# snc98_Display_15x7-Seg_1-digit_SC52.net
KiCad netlist of a schematic drawn in EAGLE
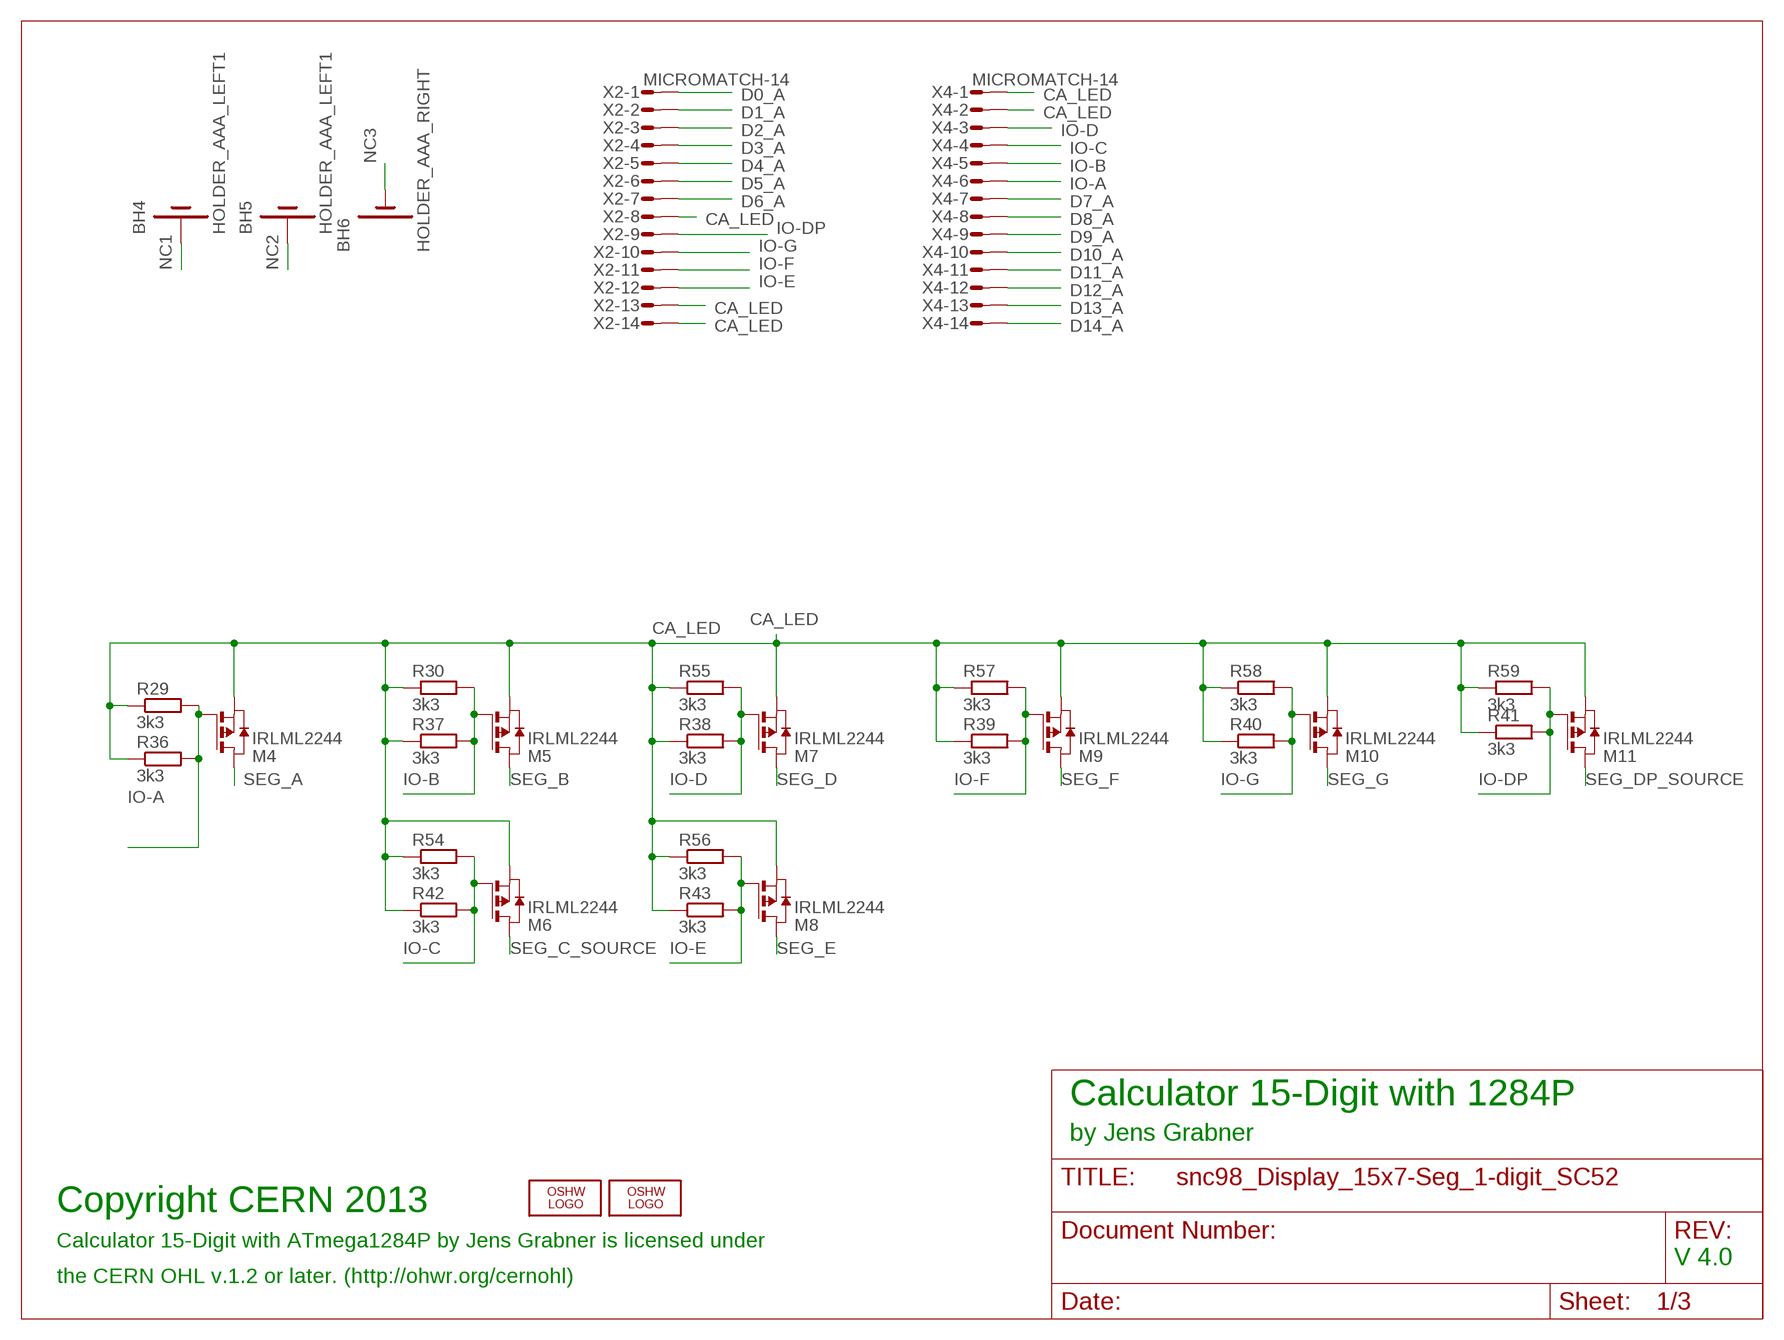
[diagram p0: schematic, sheet 1]
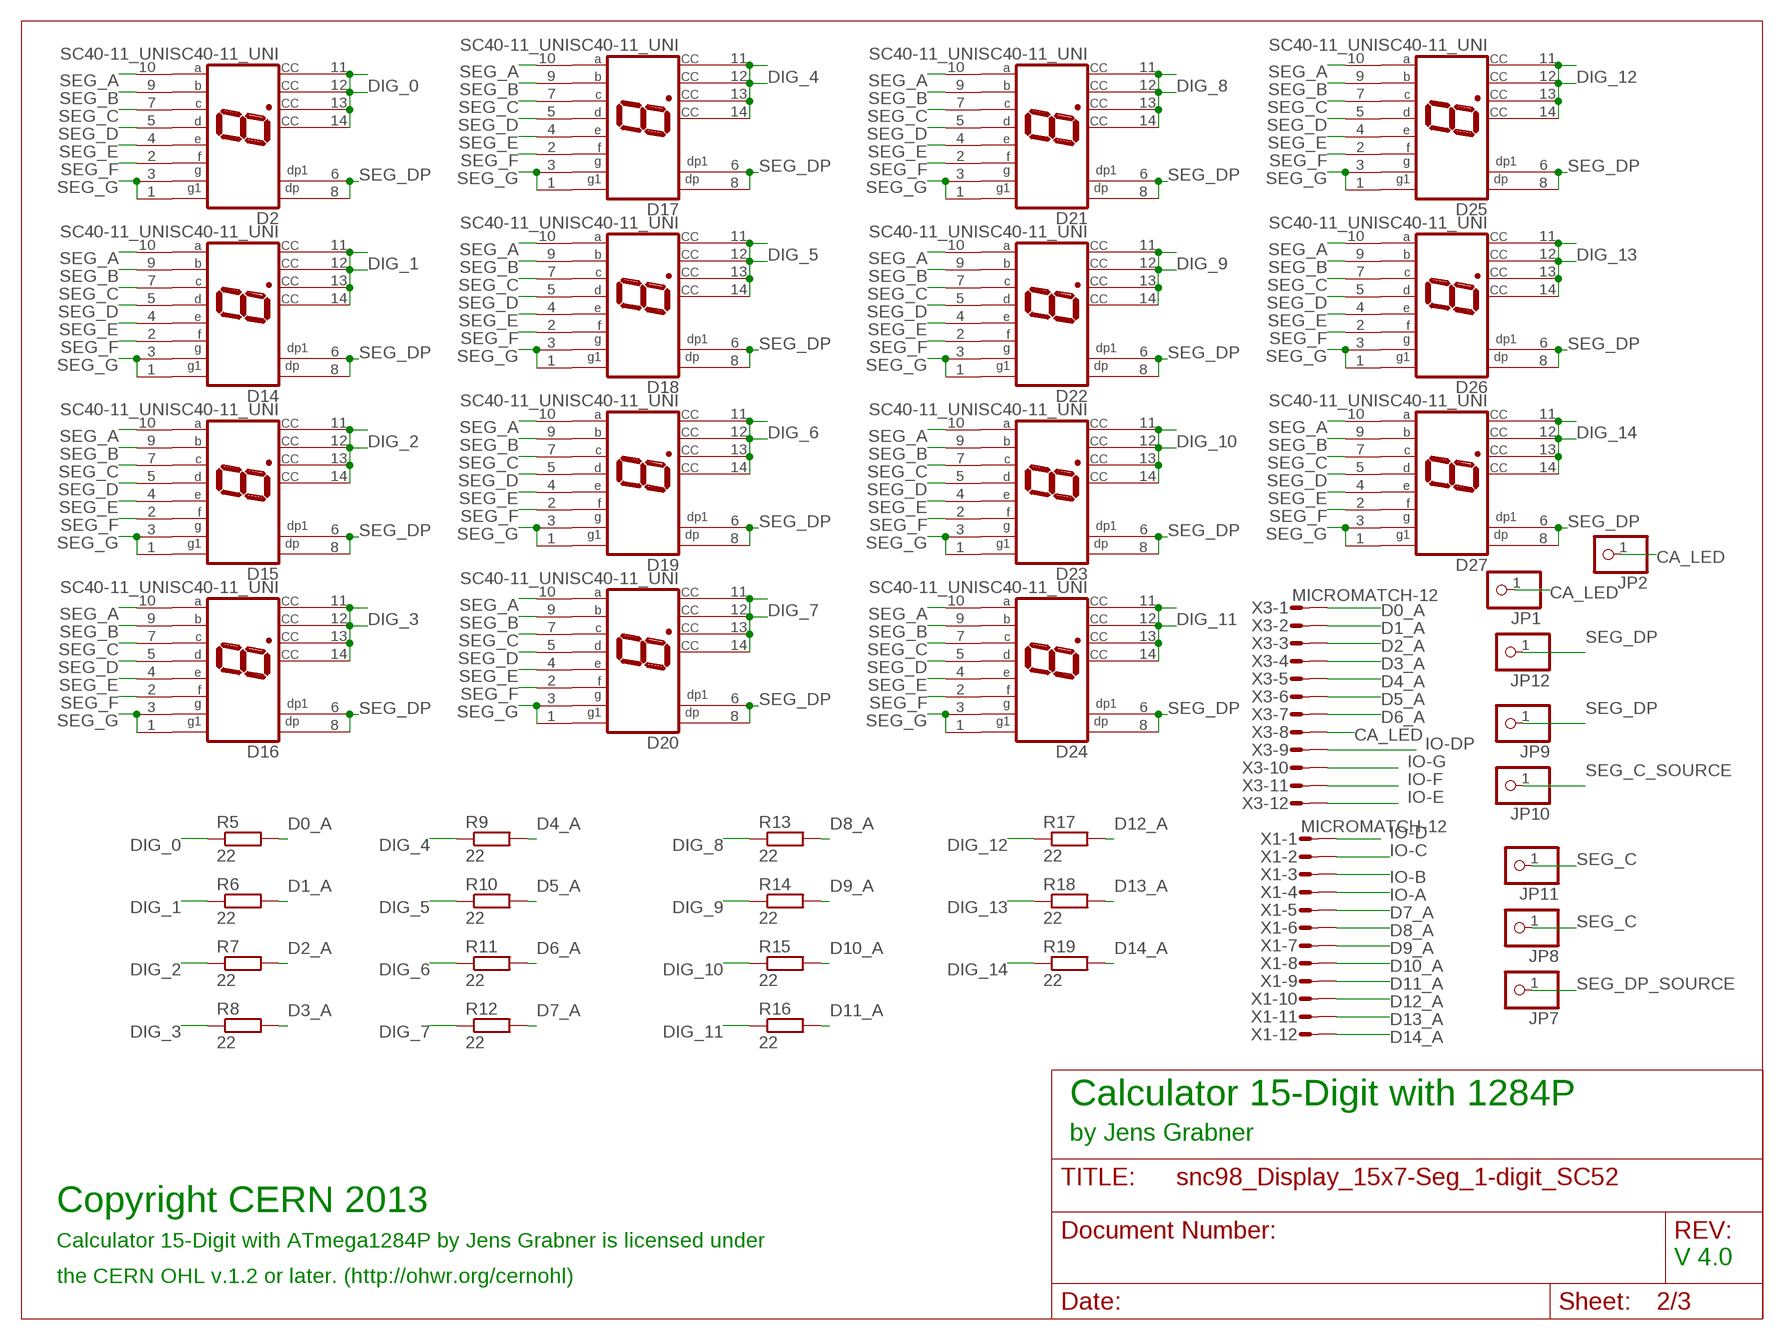
[diagram p1: schematic, sheet 2]
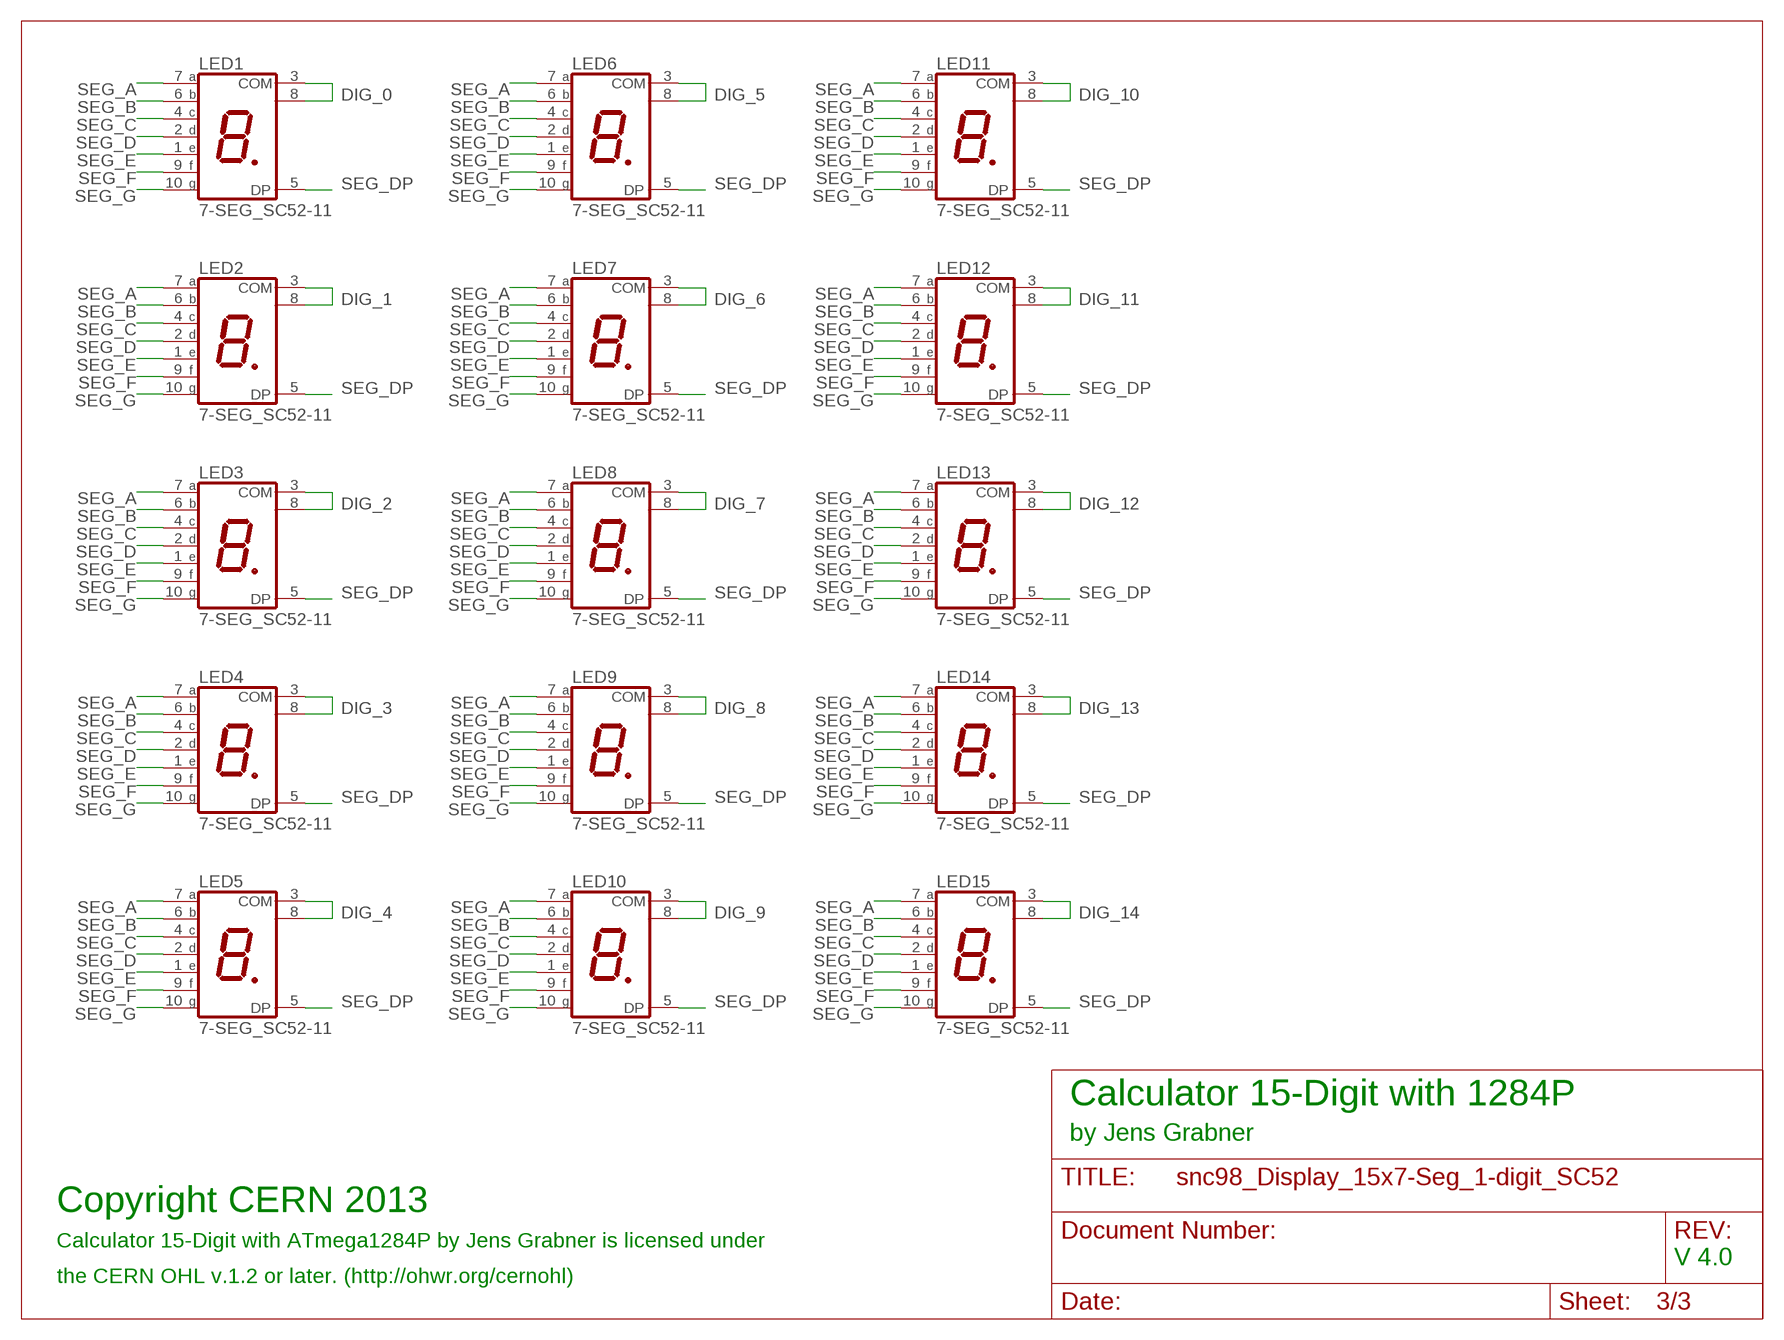
[diagram p2: schematic, sheet 3]

(export (version "E")
  (design (tool "Eeschema 10.0.6"))
  (components
    (comp (ref "LED1")
      (value "7-SEG_SC52-11")
      (footprint "eagle-import:SA52-11")
      (libsource (lib "eagle-import") (part "7-SEG_SA52-11"))
    )
    (comp (ref "LED2")
      (value "7-SEG_SC52-11")
      (footprint "eagle-import:SA52-11")
      (libsource (lib "eagle-import") (part "7-SEG_SA52-11"))
    )
    (comp (ref "LED3")
      (value "7-SEG_SC52-11")
      (footprint "eagle-import:SA52-11")
      (libsource (lib "eagle-import") (part "7-SEG_SA52-11"))
    )
    (comp (ref "LED4")
      (value "7-SEG_SC52-11")
      (footprint "eagle-import:SA52-11")
      (libsource (lib "eagle-import") (part "7-SEG_SA52-11"))
    )
    (comp (ref "LED5")
      (value "7-SEG_SC52-11")
      (footprint "eagle-import:SA52-11")
      (libsource (lib "eagle-import") (part "7-SEG_SA52-11"))
    )
    (comp (ref "LED6")
      (value "7-SEG_SC52-11")
      (footprint "eagle-import:SA52-11")
      (libsource (lib "eagle-import") (part "7-SEG_SA52-11"))
    )
    (comp (ref "LED7")
      (value "7-SEG_SC52-11")
      (footprint "eagle-import:SA52-11")
      (libsource (lib "eagle-import") (part "7-SEG_SA52-11"))
    )
    (comp (ref "LED8")
      (value "7-SEG_SC52-11")
      (footprint "eagle-import:SA52-11")
      (libsource (lib "eagle-import") (part "7-SEG_SA52-11"))
    )
    (comp (ref "LED9")
      (value "7-SEG_SC52-11")
      (footprint "eagle-import:SA52-11")
      (libsource (lib "eagle-import") (part "7-SEG_SA52-11"))
    )
    (comp (ref "LED10")
      (value "7-SEG_SC52-11")
      (footprint "eagle-import:SA52-11")
      (libsource (lib "eagle-import") (part "7-SEG_SA52-11"))
    )
    (comp (ref "LED11")
      (value "7-SEG_SC52-11")
      (footprint "eagle-import:SA52-11")
      (libsource (lib "eagle-import") (part "7-SEG_SA52-11"))
    )
    (comp (ref "LED12")
      (value "7-SEG_SC52-11")
      (footprint "eagle-import:SA52-11")
      (libsource (lib "eagle-import") (part "7-SEG_SA52-11"))
    )
    (comp (ref "LED13")
      (value "7-SEG_SC52-11")
      (footprint "eagle-import:SA52-11")
      (libsource (lib "eagle-import") (part "7-SEG_SA52-11"))
    )
    (comp (ref "LED14")
      (value "7-SEG_SC52-11")
      (footprint "eagle-import:SA52-11")
      (libsource (lib "eagle-import") (part "7-SEG_SA52-11"))
    )
    (comp (ref "LED15")
      (value "7-SEG_SC52-11")
      (footprint "eagle-import:SA52-11")
      (libsource (lib "eagle-import") (part "7-SEG_SA52-11"))
    )
    (comp (ref "D2")
      (value "SC40-11_UNISC40-11_UNI")
      (footprint "eagle-import:10MM_UNI")
      (libsource (lib "eagle-import") (part "SC40-11_UNISC40-11_UNI"))
    )
    (comp (ref "D14")
      (value "SC40-11_UNISC40-11_UNI")
      (footprint "eagle-import:10MM_UNI")
      (libsource (lib "eagle-import") (part "SC40-11_UNISC40-11_UNI"))
    )
    (comp (ref "D15")
      (value "SC40-11_UNISC40-11_UNI")
      (footprint "eagle-import:10MM_UNI")
      (libsource (lib "eagle-import") (part "SC40-11_UNISC40-11_UNI"))
    )
    (comp (ref "D16")
      (value "SC40-11_UNISC40-11_UNI")
      (footprint "eagle-import:10MM_UNI")
      (libsource (lib "eagle-import") (part "SC40-11_UNISC40-11_UNI"))
    )
    (comp (ref "D17")
      (value "SC40-11_UNISC40-11_UNI")
      (footprint "eagle-import:10MM_UNI")
      (libsource (lib "eagle-import") (part "SC40-11_UNISC40-11_UNI"))
    )
    (comp (ref "D18")
      (value "SC40-11_UNISC40-11_UNI")
      (footprint "eagle-import:10MM_UNI")
      (libsource (lib "eagle-import") (part "SC40-11_UNISC40-11_UNI"))
    )
    (comp (ref "D19")
      (value "SC40-11_UNISC40-11_UNI")
      (footprint "eagle-import:10MM_UNI")
      (libsource (lib "eagle-import") (part "SC40-11_UNISC40-11_UNI"))
    )
    (comp (ref "D20")
      (value "SC40-11_UNISC40-11_UNI")
      (footprint "eagle-import:10MM_UNI")
      (libsource (lib "eagle-import") (part "SC40-11_UNISC40-11_UNI"))
    )
    (comp (ref "D21")
      (value "SC40-11_UNISC40-11_UNI")
      (footprint "eagle-import:10MM_UNI")
      (libsource (lib "eagle-import") (part "SC40-11_UNISC40-11_UNI"))
    )
    (comp (ref "D22")
      (value "SC40-11_UNISC40-11_UNI")
      (footprint "eagle-import:10MM_UNI")
      (libsource (lib "eagle-import") (part "SC40-11_UNISC40-11_UNI"))
    )
    (comp (ref "D23")
      (value "SC40-11_UNISC40-11_UNI")
      (footprint "eagle-import:10MM_UNI")
      (libsource (lib "eagle-import") (part "SC40-11_UNISC40-11_UNI"))
    )
    (comp (ref "D24")
      (value "SC40-11_UNISC40-11_UNI")
      (footprint "eagle-import:10MM_UNI")
      (libsource (lib "eagle-import") (part "SC40-11_UNISC40-11_UNI"))
    )
    (comp (ref "D25")
      (value "SC40-11_UNISC40-11_UNI")
      (footprint "eagle-import:10MM_UNI")
      (libsource (lib "eagle-import") (part "SC40-11_UNISC40-11_UNI"))
    )
    (comp (ref "D26")
      (value "SC40-11_UNISC40-11_UNI")
      (footprint "eagle-import:10MM_UNI")
      (libsource (lib "eagle-import") (part "SC40-11_UNISC40-11_UNI"))
    )
    (comp (ref "D27")
      (value "SC40-11_UNISC40-11_UNI")
      (footprint "eagle-import:10MM_UNI")
      (libsource (lib "eagle-import") (part "SC40-11_UNISC40-11_UNI"))
    )
    (comp (ref "JP1")
      (value "PINHD-1X1")
      (footprint "eagle-import:1X01")
      (libsource (lib "eagle-import") (part "PINHD-1X1"))
    )
    (comp (ref "JP2")
      (value "PINHD-1X1")
      (footprint "eagle-import:1X01")
      (libsource (lib "eagle-import") (part "PINHD-1X1"))
    )
    (comp (ref "JP7")
      (value "PINHD-1X1")
      (footprint "eagle-import:1X01")
      (libsource (lib "eagle-import") (part "PINHD-1X1"))
    )
    (comp (ref "JP8")
      (value "PINHD-1X1")
      (footprint "eagle-import:1X01")
      (libsource (lib "eagle-import") (part "PINHD-1X1"))
    )
    (comp (ref "JP9")
      (value "PINHD-1X1")
      (footprint "eagle-import:1X01")
      (libsource (lib "eagle-import") (part "PINHD-1X1"))
    )
    (comp (ref "JP10")
      (value "PINHD-1X1")
      (footprint "eagle-import:1X01")
      (libsource (lib "eagle-import") (part "PINHD-1X1"))
    )
    (comp (ref "JP11")
      (value "PINHD-1X1")
      (footprint "eagle-import:1X01")
      (libsource (lib "eagle-import") (part "PINHD-1X1"))
    )
    (comp (ref "JP12")
      (value "PINHD-1X1")
      (footprint "eagle-import:1X01")
      (libsource (lib "eagle-import") (part "PINHD-1X1"))
    )
    (comp (ref "R5")
      (value "22")
      (footprint "eagle-import:R1210")
      (libsource (lib "eagle-import") (part "R-EU_R1210"))
    )
    (comp (ref "R6")
      (value "22")
      (footprint "eagle-import:R1210")
      (libsource (lib "eagle-import") (part "R-EU_R1210"))
    )
    (comp (ref "R7")
      (value "22")
      (footprint "eagle-import:R1210")
      (libsource (lib "eagle-import") (part "R-EU_R1210"))
    )
    (comp (ref "R8")
      (value "22")
      (footprint "eagle-import:R1210")
      (libsource (lib "eagle-import") (part "R-EU_R1210"))
    )
    (comp (ref "R9")
      (value "22")
      (footprint "eagle-import:R1210")
      (libsource (lib "eagle-import") (part "R-EU_R1210"))
    )
    (comp (ref "R10")
      (value "22")
      (footprint "eagle-import:R1210")
      (libsource (lib "eagle-import") (part "R-EU_R1210"))
    )
    (comp (ref "R11")
      (value "22")
      (footprint "eagle-import:R1210")
      (libsource (lib "eagle-import") (part "R-EU_R1210"))
    )
    (comp (ref "R12")
      (value "22")
      (footprint "eagle-import:R1210")
      (libsource (lib "eagle-import") (part "R-EU_R1210"))
    )
    (comp (ref "R13")
      (value "22")
      (footprint "eagle-import:R1210")
      (libsource (lib "eagle-import") (part "R-EU_R1210"))
    )
    (comp (ref "R14")
      (value "22")
      (footprint "eagle-import:R1210")
      (libsource (lib "eagle-import") (part "R-EU_R1210"))
    )
    (comp (ref "R15")
      (value "22")
      (footprint "eagle-import:R1210")
      (libsource (lib "eagle-import") (part "R-EU_R1210"))
    )
    (comp (ref "R16")
      (value "22")
      (footprint "eagle-import:R1210")
      (libsource (lib "eagle-import") (part "R-EU_R1210"))
    )
    (comp (ref "R17")
      (value "22")
      (footprint "eagle-import:R1210")
      (libsource (lib "eagle-import") (part "R-EU_R1210"))
    )
    (comp (ref "R18")
      (value "22")
      (footprint "eagle-import:R1210")
      (libsource (lib "eagle-import") (part "R-EU_R1210"))
    )
    (comp (ref "R19")
      (value "22")
      (footprint "eagle-import:R1210")
      (libsource (lib "eagle-import") (part "R-EU_R1210"))
    )
    (comp (ref "X1")
      (value "MICROMATCH-12")
      (footprint "eagle-import:MICROMATCH-12")
      (fields (field (name "MF") "FARNELL") (field (name "MPN") "8-215464-2"))
      (libsource (lib "eagle-import") (part "MICROMATCH-12"))
    )
    (comp (ref "X3")
      (value "MICROMATCH-12")
      (footprint "eagle-import:MICROMATCH-12")
      (fields (field (name "MF") "FARNELL") (field (name "MPN") "8-215464-2"))
      (libsource (lib "eagle-import") (part "MICROMATCH-12"))
    )
    (comp (ref "BH4")
      (value "HOLDER_AAA_LEFT1")
      (footprint "eagle-import:BATTERY-AAA-LEFT")
      (libsource (lib "eagle-import") (part "HOLDER_AAA_LEFT1"))
    )
    (comp (ref "BH5")
      (value "HOLDER_AAA_LEFT1")
      (footprint "eagle-import:BATTERY-AAA-LEFT")
      (libsource (lib "eagle-import") (part "HOLDER_AAA_LEFT1"))
    )
    (comp (ref "BH6")
      (value "HOLDER_AAA_RIGHT")
      (footprint "eagle-import:BATTERY-AAA-RIGHT")
      (libsource (lib "eagle-import") (part "HOLDER_AAA_RIGHT"))
    )
    (comp (ref "LOGO1")
      (value "OSHW_LOGO_8MILX0150-NT")
      (footprint "eagle-import:OSHW_8X150_NOTEXT")
      (libsource (lib "eagle-import") (part "OSHW_LOGO_8MILX0150-NT"))
    )
    (comp (ref "LOGO3")
      (value "OSHW_LOGO_6MILX0100-NT")
      (footprint "eagle-import:OSHW_6X100_NOTEXT")
      (libsource (lib "eagle-import") (part "OSHW_LOGO_6MILX0100-NT"))
    )
    (comp (ref "M4")
      (value "IRLML2244")
      (footprint "eagle-import:SOT-23")
      (libsource (lib "eagle-import") (part "IRLML6402"))
    )
    (comp (ref "M5")
      (value "IRLML2244")
      (footprint "eagle-import:SOT-23")
      (libsource (lib "eagle-import") (part "IRLML6402"))
    )
    (comp (ref "M6")
      (value "IRLML2244")
      (footprint "eagle-import:SOT-23")
      (libsource (lib "eagle-import") (part "IRLML6402"))
    )
    (comp (ref "M7")
      (value "IRLML2244")
      (footprint "eagle-import:SOT-23")
      (libsource (lib "eagle-import") (part "IRLML6402"))
    )
    (comp (ref "M8")
      (value "IRLML2244")
      (footprint "eagle-import:SOT-23")
      (libsource (lib "eagle-import") (part "IRLML6402"))
    )
    (comp (ref "M9")
      (value "IRLML2244")
      (footprint "eagle-import:SOT-23")
      (libsource (lib "eagle-import") (part "IRLML6402"))
    )
    (comp (ref "M10")
      (value "IRLML2244")
      (footprint "eagle-import:SOT-23")
      (libsource (lib "eagle-import") (part "IRLML6402"))
    )
    (comp (ref "M11")
      (value "IRLML2244")
      (footprint "eagle-import:SOT-23")
      (libsource (lib "eagle-import") (part "IRLML6402"))
    )
    (comp (ref "R29")
      (value "3k3")
      (footprint "eagle-import:0204_5")
      (libsource (lib "eagle-import") (part "R-EU_0204/5"))
    )
    (comp (ref "R30")
      (value "3k3")
      (footprint "eagle-import:0204_5")
      (libsource (lib "eagle-import") (part "R-EU_0204/5"))
    )
    (comp (ref "R36")
      (value "3k3")
      (footprint "eagle-import:R1206")
      (libsource (lib "eagle-import") (part "R-EU_R1206"))
    )
    (comp (ref "R37")
      (value "3k3")
      (footprint "eagle-import:R1206")
      (libsource (lib "eagle-import") (part "R-EU_R1206"))
    )
    (comp (ref "R38")
      (value "3k3")
      (footprint "eagle-import:R1206")
      (libsource (lib "eagle-import") (part "R-EU_R1206"))
    )
    (comp (ref "R39")
      (value "3k3")
      (footprint "eagle-import:R1206")
      (libsource (lib "eagle-import") (part "R-EU_R1206"))
    )
    (comp (ref "R40")
      (value "3k3")
      (footprint "eagle-import:R1206")
      (libsource (lib "eagle-import") (part "R-EU_R1206"))
    )
    (comp (ref "R41")
      (value "3k3")
      (footprint "eagle-import:R1206")
      (libsource (lib "eagle-import") (part "R-EU_R1206"))
    )
    (comp (ref "R42")
      (value "3k3")
      (footprint "eagle-import:R1206")
      (libsource (lib "eagle-import") (part "R-EU_R1206"))
    )
    (comp (ref "R43")
      (value "3k3")
      (footprint "eagle-import:R1206")
      (libsource (lib "eagle-import") (part "R-EU_R1206"))
    )
    (comp (ref "R54")
      (value "3k3")
      (footprint "eagle-import:0204_5")
      (libsource (lib "eagle-import") (part "R-EU_0204/5"))
    )
    (comp (ref "R55")
      (value "3k3")
      (footprint "eagle-import:0204_5")
      (libsource (lib "eagle-import") (part "R-EU_0204/5"))
    )
    (comp (ref "R56")
      (value "3k3")
      (footprint "eagle-import:0204_5")
      (libsource (lib "eagle-import") (part "R-EU_0204/5"))
    )
    (comp (ref "R57")
      (value "3k3")
      (footprint "eagle-import:0204_5")
      (libsource (lib "eagle-import") (part "R-EU_0204/5"))
    )
    (comp (ref "R58")
      (value "3k3")
      (footprint "eagle-import:0204_5")
      (libsource (lib "eagle-import") (part "R-EU_0204/5"))
    )
    (comp (ref "R59")
      (value "3k3")
      (footprint "eagle-import:0204_5")
      (libsource (lib "eagle-import") (part "R-EU_0204/5"))
    )
    (comp (ref "X2")
      (value "MICROMATCH-14")
      (footprint "eagle-import:MICROMATCH-14")
      (fields (field (name "MF") "FARNELL") (field (name "MPN") "8-215464-4"))
      (libsource (lib "eagle-import") (part "MICROMATCH-14"))
    )
    (comp (ref "X4")
      (value "MICROMATCH-14")
      (footprint "eagle-import:MICROMATCH-14")
      (fields (field (name "MF") "FARNELL") (field (name "MPN") "8-215464-4"))
      (libsource (lib "eagle-import") (part "MICROMATCH-14"))
    )
  )
  (nets
    (net (code "1") (name "CA_LED") (class "Default")
      (node (ref "JP1") (pin "1") (pinfunction "1_1") (pintype "passive"))
      (node (ref "JP2") (pin "1") (pinfunction "1_1") (pintype "passive"))
      (node (ref "M10") (pin "2") (pinfunction "S_2") (pintype "passive"))
      (node (ref "M11") (pin "2") (pinfunction "S_2") (pintype "passive"))
      (node (ref "M4") (pin "2") (pinfunction "S_2") (pintype "passive"))
      (node (ref "M5") (pin "2") (pinfunction "S_2") (pintype "passive"))
      (node (ref "M6") (pin "2") (pinfunction "S_2") (pintype "passive"))
      (node (ref "M7") (pin "2") (pinfunction "S_2") (pintype "passive"))
      (node (ref "M8") (pin "2") (pinfunction "S_2") (pintype "passive"))
      (node (ref "M9") (pin "2") (pinfunction "S_2") (pintype "passive"))
      (node (ref "R29") (pin "1") (pinfunction "1_1") (pintype "passive"))
      (node (ref "R30") (pin "1") (pinfunction "1_1") (pintype "passive"))
      (node (ref "R36") (pin "1") (pinfunction "1_1") (pintype "passive"))
      (node (ref "R37") (pin "1") (pinfunction "1_1") (pintype "passive"))
      (node (ref "R38") (pin "1") (pinfunction "1_1") (pintype "passive"))
      (node (ref "R39") (pin "1") (pinfunction "1_1") (pintype "passive"))
      (node (ref "R40") (pin "1") (pinfunction "1_1") (pintype "passive"))
      (node (ref "R41") (pin "1") (pinfunction "1_1") (pintype "passive"))
      (node (ref "R42") (pin "1") (pinfunction "1_1") (pintype "passive"))
      (node (ref "R43") (pin "1") (pinfunction "1_1") (pintype "passive"))
      (node (ref "R54") (pin "1") (pinfunction "1_1") (pintype "passive"))
      (node (ref "R55") (pin "1") (pinfunction "1_1") (pintype "passive"))
      (node (ref "R56") (pin "1") (pinfunction "1_1") (pintype "passive"))
      (node (ref "R57") (pin "1") (pinfunction "1_1") (pintype "passive"))
      (node (ref "R58") (pin "1") (pinfunction "1_1") (pintype "passive"))
      (node (ref "R59") (pin "1") (pinfunction "1_1") (pintype "passive"))
      (node (ref "X2") (pin "13") (pinfunction "S_13") (pintype "passive"))
      (node (ref "X2") (pin "14") (pinfunction "S_14") (pintype "passive"))
      (node (ref "X2") (pin "8") (pinfunction "S_8") (pintype "passive"))
      (node (ref "X3") (pin "8") (pinfunction "S_8") (pintype "passive"))
      (node (ref "X4") (pin "1") (pinfunction "S_1") (pintype "passive"))
      (node (ref "X4") (pin "2") (pinfunction "S_2") (pintype "passive"))
    )
    (net (code "2") (name "D0_A") (class "Default")
      (node (ref "R5") (pin "2") (pinfunction "2_2") (pintype "passive"))
      (node (ref "X2") (pin "1") (pinfunction "S_1") (pintype "passive"))
      (node (ref "X3") (pin "1") (pinfunction "S_1") (pintype "passive"))
    )
    (net (code "3") (name "D1_A") (class "Default")
      (node (ref "R6") (pin "2") (pinfunction "2_2") (pintype "passive"))
      (node (ref "X2") (pin "2") (pinfunction "S_2") (pintype "passive"))
      (node (ref "X3") (pin "2") (pinfunction "S_2") (pintype "passive"))
    )
    (net (code "4") (name "D2_A") (class "Default")
      (node (ref "R7") (pin "2") (pinfunction "2_2") (pintype "passive"))
      (node (ref "X2") (pin "3") (pinfunction "S_3") (pintype "passive"))
      (node (ref "X3") (pin "3") (pinfunction "S_3") (pintype "passive"))
    )
    (net (code "5") (name "D3_A") (class "Default")
      (node (ref "R8") (pin "2") (pinfunction "2_2") (pintype "passive"))
      (node (ref "X2") (pin "4") (pinfunction "S_4") (pintype "passive"))
      (node (ref "X3") (pin "4") (pinfunction "S_4") (pintype "passive"))
    )
    (net (code "6") (name "D4_A") (class "Default")
      (node (ref "R9") (pin "2") (pinfunction "2_2") (pintype "passive"))
      (node (ref "X2") (pin "5") (pinfunction "S_5") (pintype "passive"))
      (node (ref "X3") (pin "5") (pinfunction "S_5") (pintype "passive"))
    )
    (net (code "7") (name "D5_A") (class "Default")
      (node (ref "R10") (pin "2") (pinfunction "2_2") (pintype "passive"))
      (node (ref "X2") (pin "6") (pinfunction "S_6") (pintype "passive"))
      (node (ref "X3") (pin "6") (pinfunction "S_6") (pintype "passive"))
    )
    (net (code "8") (name "D6_A") (class "Default")
      (node (ref "R11") (pin "2") (pinfunction "2_2") (pintype "passive"))
      (node (ref "X2") (pin "7") (pinfunction "S_7") (pintype "passive"))
      (node (ref "X3") (pin "7") (pinfunction "S_7") (pintype "passive"))
    )
    (net (code "9") (name "D7_A") (class "Default")
      (node (ref "R12") (pin "2") (pinfunction "2_2") (pintype "passive"))
      (node (ref "X1") (pin "5") (pinfunction "S_5") (pintype "passive"))
      (node (ref "X4") (pin "7") (pinfunction "S_7") (pintype "passive"))
    )
    (net (code "10") (name "D8_A") (class "Default")
      (node (ref "R13") (pin "2") (pinfunction "2_2") (pintype "passive"))
      (node (ref "X1") (pin "6") (pinfunction "S_6") (pintype "passive"))
      (node (ref "X4") (pin "8") (pinfunction "S_8") (pintype "passive"))
    )
    (net (code "11") (name "D9_A") (class "Default")
      (node (ref "R14") (pin "2") (pinfunction "2_2") (pintype "passive"))
      (node (ref "X1") (pin "7") (pinfunction "S_7") (pintype "passive"))
      (node (ref "X4") (pin "9") (pinfunction "S_9") (pintype "passive"))
    )
    (net (code "12") (name "D10_A") (class "Default")
      (node (ref "R15") (pin "2") (pinfunction "2_2") (pintype "passive"))
      (node (ref "X1") (pin "8") (pinfunction "S_8") (pintype "passive"))
      (node (ref "X4") (pin "10") (pinfunction "S_10") (pintype "passive"))
    )
    (net (code "13") (name "D11_A") (class "Default")
      (node (ref "R16") (pin "2") (pinfunction "2_2") (pintype "passive"))
      (node (ref "X1") (pin "9") (pinfunction "S_9") (pintype "passive"))
      (node (ref "X4") (pin "11") (pinfunction "S_11") (pintype "passive"))
    )
    (net (code "14") (name "D12_A") (class "Default")
      (node (ref "R17") (pin "2") (pinfunction "2_2") (pintype "passive"))
      (node (ref "X1") (pin "10") (pinfunction "S_10") (pintype "passive"))
      (node (ref "X4") (pin "12") (pinfunction "S_12") (pintype "passive"))
    )
    (net (code "15") (name "D13_A") (class "Default")
      (node (ref "R18") (pin "2") (pinfunction "2_2") (pintype "passive"))
      (node (ref "X1") (pin "11") (pinfunction "S_11") (pintype "passive"))
      (node (ref "X4") (pin "13") (pinfunction "S_13") (pintype "passive"))
    )
    (net (code "16") (name "D14_A") (class "Default")
      (node (ref "R19") (pin "2") (pinfunction "2_2") (pintype "passive"))
      (node (ref "X1") (pin "12") (pinfunction "S_12") (pintype "passive"))
      (node (ref "X4") (pin "14") (pinfunction "S_14") (pintype "passive"))
    )
    (net (code "17") (name "DIG_0") (class "Default")
      (node (ref "D2") (pin "11") (pinfunction "CC1_11") (pintype "passive"))
      (node (ref "D2") (pin "12") (pinfunction "CC2_12") (pintype "passive"))
      (node (ref "D2") (pin "13") (pinfunction "CC3_13") (pintype "passive"))
      (node (ref "D2") (pin "14") (pinfunction "CC4_14") (pintype "passive"))
      (node (ref "LED1") (pin "3") (pinfunction "COM_3") (pintype "passive"))
      (node (ref "LED1") (pin "8") (pinfunction "COM_8") (pintype "passive"))
      (node (ref "R5") (pin "1") (pinfunction "1_1") (pintype "passive"))
    )
    (net (code "18") (name "DIG_1") (class "Default")
      (node (ref "D14") (pin "11") (pinfunction "CC1_11") (pintype "passive"))
      (node (ref "D14") (pin "12") (pinfunction "CC2_12") (pintype "passive"))
      (node (ref "D14") (pin "13") (pinfunction "CC3_13") (pintype "passive"))
      (node (ref "D14") (pin "14") (pinfunction "CC4_14") (pintype "passive"))
      (node (ref "LED2") (pin "3") (pinfunction "COM_3") (pintype "passive"))
      (node (ref "LED2") (pin "8") (pinfunction "COM_8") (pintype "passive"))
      (node (ref "R6") (pin "1") (pinfunction "1_1") (pintype "passive"))
    )
    (net (code "19") (name "DIG_2") (class "Default")
      (node (ref "D15") (pin "11") (pinfunction "CC1_11") (pintype "passive"))
      (node (ref "D15") (pin "12") (pinfunction "CC2_12") (pintype "passive"))
      (node (ref "D15") (pin "13") (pinfunction "CC3_13") (pintype "passive"))
      (node (ref "D15") (pin "14") (pinfunction "CC4_14") (pintype "passive"))
      (node (ref "LED3") (pin "3") (pinfunction "COM_3") (pintype "passive"))
      (node (ref "LED3") (pin "8") (pinfunction "COM_8") (pintype "passive"))
      (node (ref "R7") (pin "1") (pinfunction "1_1") (pintype "passive"))
    )
    (net (code "20") (name "DIG_3") (class "Default")
      (node (ref "D16") (pin "11") (pinfunction "CC1_11") (pintype "passive"))
      (node (ref "D16") (pin "12") (pinfunction "CC2_12") (pintype "passive"))
      (node (ref "D16") (pin "13") (pinfunction "CC3_13") (pintype "passive"))
      (node (ref "D16") (pin "14") (pinfunction "CC4_14") (pintype "passive"))
      (node (ref "LED4") (pin "3") (pinfunction "COM_3") (pintype "passive"))
      (node (ref "LED4") (pin "8") (pinfunction "COM_8") (pintype "passive"))
      (node (ref "R8") (pin "1") (pinfunction "1_1") (pintype "passive"))
    )
    (net (code "21") (name "DIG_4") (class "Default")
      (node (ref "D17") (pin "11") (pinfunction "CC1_11") (pintype "passive"))
      (node (ref "D17") (pin "12") (pinfunction "CC2_12") (pintype "passive"))
      (node (ref "D17") (pin "13") (pinfunction "CC3_13") (pintype "passive"))
      (node (ref "D17") (pin "14") (pinfunction "CC4_14") (pintype "passive"))
      (node (ref "LED5") (pin "3") (pinfunction "COM_3") (pintype "passive"))
      (node (ref "LED5") (pin "8") (pinfunction "COM_8") (pintype "passive"))
      (node (ref "R9") (pin "1") (pinfunction "1_1") (pintype "passive"))
    )
    (net (code "22") (name "DIG_5") (class "Default")
      (node (ref "D18") (pin "11") (pinfunction "CC1_11") (pintype "passive"))
      (node (ref "D18") (pin "12") (pinfunction "CC2_12") (pintype "passive"))
      (node (ref "D18") (pin "13") (pinfunction "CC3_13") (pintype "passive"))
      (node (ref "D18") (pin "14") (pinfunction "CC4_14") (pintype "passive"))
      (node (ref "LED6") (pin "3") (pinfunction "COM_3") (pintype "passive"))
      (node (ref "LED6") (pin "8") (pinfunction "COM_8") (pintype "passive"))
      (node (ref "R10") (pin "1") (pinfunction "1_1") (pintype "passive"))
    )
    (net (code "23") (name "DIG_6") (class "Default")
      (node (ref "D19") (pin "11") (pinfunction "CC1_11") (pintype "passive"))
      (node (ref "D19") (pin "12") (pinfunction "CC2_12") (pintype "passive"))
      (node (ref "D19") (pin "13") (pinfunction "CC3_13") (pintype "passive"))
      (node (ref "D19") (pin "14") (pinfunction "CC4_14") (pintype "passive"))
      (node (ref "LED7") (pin "3") (pinfunction "COM_3") (pintype "passive"))
      (node (ref "LED7") (pin "8") (pinfunction "COM_8") (pintype "passive"))
      (node (ref "R11") (pin "1") (pinfunction "1_1") (pintype "passive"))
    )
    (net (code "24") (name "DIG_7") (class "Default")
      (node (ref "D20") (pin "11") (pinfunction "CC1_11") (pintype "passive"))
      (node (ref "D20") (pin "12") (pinfunction "CC2_12") (pintype "passive"))
      (node (ref "D20") (pin "13") (pinfunction "CC3_13") (pintype "passive"))
      (node (ref "D20") (pin "14") (pinfunction "CC4_14") (pintype "passive"))
      (node (ref "LED8") (pin "3") (pinfunction "COM_3") (pintype "passive"))
      (node (ref "LED8") (pin "8") (pinfunction "COM_8") (pintype "passive"))
      (node (ref "R12") (pin "1") (pinfunction "1_1") (pintype "passive"))
    )
    (net (code "25") (name "DIG_8") (class "Default")
      (node (ref "D21") (pin "11") (pinfunction "CC1_11") (pintype "passive"))
      (node (ref "D21") (pin "12") (pinfunction "CC2_12") (pintype "passive"))
      (node (ref "D21") (pin "13") (pinfunction "CC3_13") (pintype "passive"))
      (node (ref "D21") (pin "14") (pinfunction "CC4_14") (pintype "passive"))
      (node (ref "LED9") (pin "3") (pinfunction "COM_3") (pintype "passive"))
      (node (ref "LED9") (pin "8") (pinfunction "COM_8") (pintype "passive"))
      (node (ref "R13") (pin "1") (pinfunction "1_1") (pintype "passive"))
    )
    (net (code "26") (name "DIG_9") (class "Default")
      (node (ref "D22") (pin "11") (pinfunction "CC1_11") (pintype "passive"))
      (node (ref "D22") (pin "12") (pinfunction "CC2_12") (pintype "passive"))
      (node (ref "D22") (pin "13") (pinfunction "CC3_13") (pintype "passive"))
      (node (ref "D22") (pin "14") (pinfunction "CC4_14") (pintype "passive"))
      (node (ref "LED10") (pin "3") (pinfunction "COM_3") (pintype "passive"))
      (node (ref "LED10") (pin "8") (pinfunction "COM_8") (pintype "passive"))
      (node (ref "R14") (pin "1") (pinfunction "1_1") (pintype "passive"))
    )
    (net (code "27") (name "DIG_10") (class "Default")
      (node (ref "D23") (pin "11") (pinfunction "CC1_11") (pintype "passive"))
      (node (ref "D23") (pin "12") (pinfunction "CC2_12") (pintype "passive"))
      (node (ref "D23") (pin "13") (pinfunction "CC3_13") (pintype "passive"))
      (node (ref "D23") (pin "14") (pinfunction "CC4_14") (pintype "passive"))
      (node (ref "LED11") (pin "3") (pinfunction "COM_3") (pintype "passive"))
      (node (ref "LED11") (pin "8") (pinfunction "COM_8") (pintype "passive"))
      (node (ref "R15") (pin "1") (pinfunction "1_1") (pintype "passive"))
    )
    (net (code "28") (name "DIG_11") (class "Default")
      (node (ref "D24") (pin "11") (pinfunction "CC1_11") (pintype "passive"))
      (node (ref "D24") (pin "12") (pinfunction "CC2_12") (pintype "passive"))
      (node (ref "D24") (pin "13") (pinfunction "CC3_13") (pintype "passive"))
      (node (ref "D24") (pin "14") (pinfunction "CC4_14") (pintype "passive"))
      (node (ref "LED12") (pin "3") (pinfunction "COM_3") (pintype "passive"))
      (node (ref "LED12") (pin "8") (pinfunction "COM_8") (pintype "passive"))
      (node (ref "R16") (pin "1") (pinfunction "1_1") (pintype "passive"))
    )
    (net (code "29") (name "DIG_12") (class "Default")
      (node (ref "D25") (pin "11") (pinfunction "CC1_11") (pintype "passive"))
      (node (ref "D25") (pin "12") (pinfunction "CC2_12") (pintype "passive"))
      (node (ref "D25") (pin "13") (pinfunction "CC3_13") (pintype "passive"))
      (node (ref "D25") (pin "14") (pinfunction "CC4_14") (pintype "passive"))
      (node (ref "LED13") (pin "3") (pinfunction "COM_3") (pintype "passive"))
      (node (ref "LED13") (pin "8") (pinfunction "COM_8") (pintype "passive"))
      (node (ref "R17") (pin "1") (pinfunction "1_1") (pintype "passive"))
    )
    (net (code "30") (name "DIG_13") (class "Default")
      (node (ref "D26") (pin "11") (pinfunction "CC1_11") (pintype "passive"))
      (node (ref "D26") (pin "12") (pinfunction "CC2_12") (pintype "passive"))
      (node (ref "D26") (pin "13") (pinfunction "CC3_13") (pintype "passive"))
      (node (ref "D26") (pin "14") (pinfunction "CC4_14") (pintype "passive"))
      (node (ref "LED14") (pin "3") (pinfunction "COM_3") (pintype "passive"))
      (node (ref "LED14") (pin "8") (pinfunction "COM_8") (pintype "passive"))
      (node (ref "R18") (pin "1") (pinfunction "1_1") (pintype "passive"))
    )
    (net (code "31") (name "DIG_14") (class "Default")
      (node (ref "D27") (pin "11") (pinfunction "CC1_11") (pintype "passive"))
      (node (ref "D27") (pin "12") (pinfunction "CC2_12") (pintype "passive"))
      (node (ref "D27") (pin "13") (pinfunction "CC3_13") (pintype "passive"))
      (node (ref "D27") (pin "14") (pinfunction "CC4_14") (pintype "passive"))
      (node (ref "LED15") (pin "3") (pinfunction "COM_3") (pintype "passive"))
      (node (ref "LED15") (pin "8") (pinfunction "COM_8") (pintype "passive"))
      (node (ref "R19") (pin "1") (pinfunction "1_1") (pintype "passive"))
    )
    (net (code "32") (name "IO-A") (class "Default")
      (node (ref "M4") (pin "1") (pinfunction "G_1") (pintype "passive"))
      (node (ref "R29") (pin "2") (pinfunction "2_2") (pintype "passive"))
      (node (ref "R36") (pin "2") (pinfunction "2_2") (pintype "passive"))
      (node (ref "X1") (pin "4") (pinfunction "S_4") (pintype "passive"))
      (node (ref "X4") (pin "6") (pinfunction "S_6") (pintype "passive"))
    )
    (net (code "33") (name "IO-B") (class "Default")
      (node (ref "M5") (pin "1") (pinfunction "G_1") (pintype "passive"))
      (node (ref "R30") (pin "2") (pinfunction "2_2") (pintype "passive"))
      (node (ref "R37") (pin "2") (pinfunction "2_2") (pintype "passive"))
      (node (ref "X1") (pin "3") (pinfunction "S_3") (pintype "passive"))
      (node (ref "X4") (pin "5") (pinfunction "S_5") (pintype "passive"))
    )
    (net (code "34") (name "IO-C") (class "Default")
      (node (ref "M6") (pin "1") (pinfunction "G_1") (pintype "passive"))
      (node (ref "R42") (pin "2") (pinfunction "2_2") (pintype "passive"))
      (node (ref "R54") (pin "2") (pinfunction "2_2") (pintype "passive"))
      (node (ref "X1") (pin "2") (pinfunction "S_2") (pintype "passive"))
      (node (ref "X4") (pin "4") (pinfunction "S_4") (pintype "passive"))
    )
    (net (code "35") (name "IO-D") (class "Default")
      (node (ref "M7") (pin "1") (pinfunction "G_1") (pintype "passive"))
      (node (ref "R38") (pin "2") (pinfunction "2_2") (pintype "passive"))
      (node (ref "R55") (pin "2") (pinfunction "2_2") (pintype "passive"))
      (node (ref "X1") (pin "1") (pinfunction "S_1") (pintype "passive"))
      (node (ref "X4") (pin "3") (pinfunction "S_3") (pintype "passive"))
    )
    (net (code "36") (name "IO-DP") (class "Default")
      (node (ref "M11") (pin "1") (pinfunction "G_1") (pintype "passive"))
      (node (ref "R41") (pin "2") (pinfunction "2_2") (pintype "passive"))
      (node (ref "R59") (pin "2") (pinfunction "2_2") (pintype "passive"))
      (node (ref "X2") (pin "9") (pinfunction "S_9") (pintype "passive"))
      (node (ref "X3") (pin "9") (pinfunction "S_9") (pintype "passive"))
    )
    (net (code "37") (name "IO-E") (class "Default")
      (node (ref "M8") (pin "1") (pinfunction "G_1") (pintype "passive"))
      (node (ref "R43") (pin "2") (pinfunction "2_2") (pintype "passive"))
      (node (ref "R56") (pin "2") (pinfunction "2_2") (pintype "passive"))
      (node (ref "X2") (pin "12") (pinfunction "S_12") (pintype "passive"))
      (node (ref "X3") (pin "12") (pinfunction "S_12") (pintype "passive"))
    )
    (net (code "38") (name "IO-F") (class "Default")
      (node (ref "M9") (pin "1") (pinfunction "G_1") (pintype "passive"))
      (node (ref "R39") (pin "2") (pinfunction "2_2") (pintype "passive"))
      (node (ref "R57") (pin "2") (pinfunction "2_2") (pintype "passive"))
      (node (ref "X2") (pin "11") (pinfunction "S_11") (pintype "passive"))
      (node (ref "X3") (pin "11") (pinfunction "S_11") (pintype "passive"))
    )
    (net (code "39") (name "IO-G") (class "Default")
      (node (ref "M10") (pin "1") (pinfunction "G_1") (pintype "passive"))
      (node (ref "R40") (pin "2") (pinfunction "2_2") (pintype "passive"))
      (node (ref "R58") (pin "2") (pinfunction "2_2") (pintype "passive"))
      (node (ref "X2") (pin "10") (pinfunction "S_10") (pintype "passive"))
      (node (ref "X3") (pin "10") (pinfunction "S_10") (pintype "passive"))
    )
    (net (code "40") (name "NC1") (class "Default")
      (node (ref "BH4") (pin "P1") (pinfunction "+_P1") (pintype "power_in"))
      (node (ref "BH4") (pin "P2") (pinfunction "+_P2") (pintype "power_in"))
      (node (ref "BH4") (pin "P3") (pinfunction "+_P3") (pintype "power_in"))
      (node (ref "BH4") (pin "P4") (pinfunction "+_P4") (pintype "power_in"))
    )
    (net (code "41") (name "NC2") (class "Default")
      (node (ref "BH5") (pin "P1") (pinfunction "+_P1") (pintype "power_in"))
      (node (ref "BH5") (pin "P2") (pinfunction "+_P2") (pintype "power_in"))
      (node (ref "BH5") (pin "P3") (pinfunction "+_P3") (pintype "power_in"))
      (node (ref "BH5") (pin "P4") (pinfunction "+_P4") (pintype "power_in"))
    )
    (net (code "42") (name "NC3") (class "Default")
      (node (ref "BH6") (pin "M1") (pinfunction "-_M1") (pintype "power_in"))
      (node (ref "BH6") (pin "M2") (pinfunction "-_M2") (pintype "power_in"))
      (node (ref "BH6") (pin "M3") (pinfunction "-_M3") (pintype "power_in"))
      (node (ref "BH6") (pin "M4") (pinfunction "-_M4") (pintype "power_in"))
    )
    (net (code "43") (name "SEG_A") (class "Default")
      (node (ref "D14") (pin "10") (pinfunction "A_10") (pintype "passive"))
      (node (ref "D15") (pin "10") (pinfunction "A_10") (pintype "passive"))
      (node (ref "D16") (pin "10") (pinfunction "A_10") (pintype "passive"))
      (node (ref "D17") (pin "10") (pinfunction "A_10") (pintype "passive"))
      (node (ref "D18") (pin "10") (pinfunction "A_10") (pintype "passive"))
      (node (ref "D19") (pin "10") (pinfunction "A_10") (pintype "passive"))
      (node (ref "D2") (pin "10") (pinfunction "A_10") (pintype "passive"))
      (node (ref "D20") (pin "10") (pinfunction "A_10") (pintype "passive"))
      (node (ref "D21") (pin "10") (pinfunction "A_10") (pintype "passive"))
      (node (ref "D22") (pin "10") (pinfunction "A_10") (pintype "passive"))
      (node (ref "D23") (pin "10") (pinfunction "A_10") (pintype "passive"))
      (node (ref "D24") (pin "10") (pinfunction "A_10") (pintype "passive"))
      (node (ref "D25") (pin "10") (pinfunction "A_10") (pintype "passive"))
      (node (ref "D26") (pin "10") (pinfunction "A_10") (pintype "passive"))
      (node (ref "D27") (pin "10") (pinfunction "A_10") (pintype "passive"))
      (node (ref "LED1") (pin "7") (pinfunction "A_7") (pintype "passive"))
      (node (ref "LED10") (pin "7") (pinfunction "A_7") (pintype "passive"))
      (node (ref "LED11") (pin "7") (pinfunction "A_7") (pintype "passive"))
      (node (ref "LED12") (pin "7") (pinfunction "A_7") (pintype "passive"))
      (node (ref "LED13") (pin "7") (pinfunction "A_7") (pintype "passive"))
      (node (ref "LED14") (pin "7") (pinfunction "A_7") (pintype "passive"))
      (node (ref "LED15") (pin "7") (pinfunction "A_7") (pintype "passive"))
      (node (ref "LED2") (pin "7") (pinfunction "A_7") (pintype "passive"))
      (node (ref "LED3") (pin "7") (pinfunction "A_7") (pintype "passive"))
      (node (ref "LED4") (pin "7") (pinfunction "A_7") (pintype "passive"))
      (node (ref "LED5") (pin "7") (pinfunction "A_7") (pintype "passive"))
      (node (ref "LED6") (pin "7") (pinfunction "A_7") (pintype "passive"))
      (node (ref "LED7") (pin "7") (pinfunction "A_7") (pintype "passive"))
      (node (ref "LED8") (pin "7") (pinfunction "A_7") (pintype "passive"))
      (node (ref "LED9") (pin "7") (pinfunction "A_7") (pintype "passive"))
      (node (ref "M4") (pin "3") (pinfunction "D_3") (pintype "passive"))
    )
    (net (code "44") (name "SEG_B") (class "Default")
      (node (ref "D14") (pin "9") (pinfunction "B_9") (pintype "passive"))
      (node (ref "D15") (pin "9") (pinfunction "B_9") (pintype "passive"))
      (node (ref "D16") (pin "9") (pinfunction "B_9") (pintype "passive"))
      (node (ref "D17") (pin "9") (pinfunction "B_9") (pintype "passive"))
      (node (ref "D18") (pin "9") (pinfunction "B_9") (pintype "passive"))
      (node (ref "D19") (pin "9") (pinfunction "B_9") (pintype "passive"))
      (node (ref "D2") (pin "9") (pinfunction "B_9") (pintype "passive"))
      (node (ref "D20") (pin "9") (pinfunction "B_9") (pintype "passive"))
      (node (ref "D21") (pin "9") (pinfunction "B_9") (pintype "passive"))
      (node (ref "D22") (pin "9") (pinfunction "B_9") (pintype "passive"))
      (node (ref "D23") (pin "9") (pinfunction "B_9") (pintype "passive"))
      (node (ref "D24") (pin "9") (pinfunction "B_9") (pintype "passive"))
      (node (ref "D25") (pin "9") (pinfunction "B_9") (pintype "passive"))
      (node (ref "D26") (pin "9") (pinfunction "B_9") (pintype "passive"))
      (node (ref "D27") (pin "9") (pinfunction "B_9") (pintype "passive"))
      (node (ref "LED1") (pin "6") (pinfunction "B_6") (pintype "passive"))
      (node (ref "LED10") (pin "6") (pinfunction "B_6") (pintype "passive"))
      (node (ref "LED11") (pin "6") (pinfunction "B_6") (pintype "passive"))
      (node (ref "LED12") (pin "6") (pinfunction "B_6") (pintype "passive"))
      (node (ref "LED13") (pin "6") (pinfunction "B_6") (pintype "passive"))
      (node (ref "LED14") (pin "6") (pinfunction "B_6") (pintype "passive"))
      (node (ref "LED15") (pin "6") (pinfunction "B_6") (pintype "passive"))
      (node (ref "LED2") (pin "6") (pinfunction "B_6") (pintype "passive"))
      (node (ref "LED3") (pin "6") (pinfunction "B_6") (pintype "passive"))
      (node (ref "LED4") (pin "6") (pinfunction "B_6") (pintype "passive"))
      (node (ref "LED5") (pin "6") (pinfunction "B_6") (pintype "passive"))
      (node (ref "LED6") (pin "6") (pinfunction "B_6") (pintype "passive"))
      (node (ref "LED7") (pin "6") (pinfunction "B_6") (pintype "passive"))
      (node (ref "LED8") (pin "6") (pinfunction "B_6") (pintype "passive"))
      (node (ref "LED9") (pin "6") (pinfunction "B_6") (pintype "passive"))
      (node (ref "M5") (pin "3") (pinfunction "D_3") (pintype "passive"))
    )
    (net (code "45") (name "SEG_C") (class "Default")
      (node (ref "D14") (pin "7") (pinfunction "C_7") (pintype "passive"))
      (node (ref "D15") (pin "7") (pinfunction "C_7") (pintype "passive"))
      (node (ref "D16") (pin "7") (pinfunction "C_7") (pintype "passive"))
      (node (ref "D17") (pin "7") (pinfunction "C_7") (pintype "passive"))
      (node (ref "D18") (pin "7") (pinfunction "C_7") (pintype "passive"))
      (node (ref "D19") (pin "7") (pinfunction "C_7") (pintype "passive"))
      (node (ref "D2") (pin "7") (pinfunction "C_7") (pintype "passive"))
      (node (ref "D20") (pin "7") (pinfunction "C_7") (pintype "passive"))
      (node (ref "D21") (pin "7") (pinfunction "C_7") (pintype "passive"))
      (node (ref "D22") (pin "7") (pinfunction "C_7") (pintype "passive"))
      (node (ref "D23") (pin "7") (pinfunction "C_7") (pintype "passive"))
      (node (ref "D24") (pin "7") (pinfunction "C_7") (pintype "passive"))
      (node (ref "D25") (pin "7") (pinfunction "C_7") (pintype "passive"))
      (node (ref "D26") (pin "7") (pinfunction "C_7") (pintype "passive"))
      (node (ref "D27") (pin "7") (pinfunction "C_7") (pintype "passive"))
      (node (ref "JP11") (pin "1") (pinfunction "1_1") (pintype "passive"))
      (node (ref "JP8") (pin "1") (pinfunction "1_1") (pintype "passive"))
      (node (ref "LED1") (pin "4") (pinfunction "C_4") (pintype "passive"))
      (node (ref "LED10") (pin "4") (pinfunction "C_4") (pintype "passive"))
      (node (ref "LED11") (pin "4") (pinfunction "C_4") (pintype "passive"))
      (node (ref "LED12") (pin "4") (pinfunction "C_4") (pintype "passive"))
      (node (ref "LED13") (pin "4") (pinfunction "C_4") (pintype "passive"))
      (node (ref "LED14") (pin "4") (pinfunction "C_4") (pintype "passive"))
      (node (ref "LED15") (pin "4") (pinfunction "C_4") (pintype "passive"))
      (node (ref "LED2") (pin "4") (pinfunction "C_4") (pintype "passive"))
      (node (ref "LED3") (pin "4") (pinfunction "C_4") (pintype "passive"))
      (node (ref "LED4") (pin "4") (pinfunction "C_4") (pintype "passive"))
      (node (ref "LED5") (pin "4") (pinfunction "C_4") (pintype "passive"))
      (node (ref "LED6") (pin "4") (pinfunction "C_4") (pintype "passive"))
      (node (ref "LED7") (pin "4") (pinfunction "C_4") (pintype "passive"))
      (node (ref "LED8") (pin "4") (pinfunction "C_4") (pintype "passive"))
      (node (ref "LED9") (pin "4") (pinfunction "C_4") (pintype "passive"))
    )
    (net (code "46") (name "SEG_C_SOURCE") (class "Default")
      (node (ref "JP10") (pin "1") (pinfunction "1_1") (pintype "passive"))
      (node (ref "M6") (pin "3") (pinfunction "D_3") (pintype "passive"))
    )
    (net (code "47") (name "SEG_D") (class "Default")
      (node (ref "D14") (pin "5") (pinfunction "D_5") (pintype "passive"))
      (node (ref "D15") (pin "5") (pinfunction "D_5") (pintype "passive"))
      (node (ref "D16") (pin "5") (pinfunction "D_5") (pintype "passive"))
      (node (ref "D17") (pin "5") (pinfunction "D_5") (pintype "passive"))
      (node (ref "D18") (pin "5") (pinfunction "D_5") (pintype "passive"))
      (node (ref "D19") (pin "5") (pinfunction "D_5") (pintype "passive"))
      (node (ref "D2") (pin "5") (pinfunction "D_5") (pintype "passive"))
      (node (ref "D20") (pin "5") (pinfunction "D_5") (pintype "passive"))
      (node (ref "D21") (pin "5") (pinfunction "D_5") (pintype "passive"))
      (node (ref "D22") (pin "5") (pinfunction "D_5") (pintype "passive"))
      (node (ref "D23") (pin "5") (pinfunction "D_5") (pintype "passive"))
      (node (ref "D24") (pin "5") (pinfunction "D_5") (pintype "passive"))
      (node (ref "D25") (pin "5") (pinfunction "D_5") (pintype "passive"))
      (node (ref "D26") (pin "5") (pinfunction "D_5") (pintype "passive"))
      (node (ref "D27") (pin "5") (pinfunction "D_5") (pintype "passive"))
      (node (ref "LED1") (pin "2") (pinfunction "D_2") (pintype "passive"))
      (node (ref "LED10") (pin "2") (pinfunction "D_2") (pintype "passive"))
      (node (ref "LED11") (pin "2") (pinfunction "D_2") (pintype "passive"))
      (node (ref "LED12") (pin "2") (pinfunction "D_2") (pintype "passive"))
      (node (ref "LED13") (pin "2") (pinfunction "D_2") (pintype "passive"))
      (node (ref "LED14") (pin "2") (pinfunction "D_2") (pintype "passive"))
      (node (ref "LED15") (pin "2") (pinfunction "D_2") (pintype "passive"))
      (node (ref "LED2") (pin "2") (pinfunction "D_2") (pintype "passive"))
      (node (ref "LED3") (pin "2") (pinfunction "D_2") (pintype "passive"))
      (node (ref "LED4") (pin "2") (pinfunction "D_2") (pintype "passive"))
      (node (ref "LED5") (pin "2") (pinfunction "D_2") (pintype "passive"))
      (node (ref "LED6") (pin "2") (pinfunction "D_2") (pintype "passive"))
      (node (ref "LED7") (pin "2") (pinfunction "D_2") (pintype "passive"))
      (node (ref "LED8") (pin "2") (pinfunction "D_2") (pintype "passive"))
      (node (ref "LED9") (pin "2") (pinfunction "D_2") (pintype "passive"))
      (node (ref "M7") (pin "3") (pinfunction "D_3") (pintype "passive"))
    )
    (net (code "48") (name "SEG_DP") (class "Default")
      (node (ref "D14") (pin "6") (pinfunction "DP1_6") (pintype "passive"))
      (node (ref "D14") (pin "8") (pinfunction "DP_8") (pintype "passive"))
      (node (ref "D15") (pin "6") (pinfunction "DP1_6") (pintype "passive"))
      (node (ref "D15") (pin "8") (pinfunction "DP_8") (pintype "passive"))
      (node (ref "D16") (pin "6") (pinfunction "DP1_6") (pintype "passive"))
      (node (ref "D16") (pin "8") (pinfunction "DP_8") (pintype "passive"))
      (node (ref "D17") (pin "6") (pinfunction "DP1_6") (pintype "passive"))
      (node (ref "D17") (pin "8") (pinfunction "DP_8") (pintype "passive"))
      (node (ref "D18") (pin "6") (pinfunction "DP1_6") (pintype "passive"))
      (node (ref "D18") (pin "8") (pinfunction "DP_8") (pintype "passive"))
      (node (ref "D19") (pin "6") (pinfunction "DP1_6") (pintype "passive"))
      (node (ref "D19") (pin "8") (pinfunction "DP_8") (pintype "passive"))
      (node (ref "D2") (pin "6") (pinfunction "DP1_6") (pintype "passive"))
      (node (ref "D2") (pin "8") (pinfunction "DP_8") (pintype "passive"))
      (node (ref "D20") (pin "6") (pinfunction "DP1_6") (pintype "passive"))
      (node (ref "D20") (pin "8") (pinfunction "DP_8") (pintype "passive"))
      (node (ref "D21") (pin "6") (pinfunction "DP1_6") (pintype "passive"))
      (node (ref "D21") (pin "8") (pinfunction "DP_8") (pintype "passive"))
      (node (ref "D22") (pin "6") (pinfunction "DP1_6") (pintype "passive"))
      (node (ref "D22") (pin "8") (pinfunction "DP_8") (pintype "passive"))
      (node (ref "D23") (pin "6") (pinfunction "DP1_6") (pintype "passive"))
      (node (ref "D23") (pin "8") (pinfunction "DP_8") (pintype "passive"))
      (node (ref "D24") (pin "6") (pinfunction "DP1_6") (pintype "passive"))
      (node (ref "D24") (pin "8") (pinfunction "DP_8") (pintype "passive"))
      (node (ref "D25") (pin "6") (pinfunction "DP1_6") (pintype "passive"))
      (node (ref "D25") (pin "8") (pinfunction "DP_8") (pintype "passive"))
      (node (ref "D26") (pin "6") (pinfunction "DP1_6") (pintype "passive"))
      (node (ref "D26") (pin "8") (pinfunction "DP_8") (pintype "passive"))
      (node (ref "D27") (pin "6") (pinfunction "DP1_6") (pintype "passive"))
      (node (ref "D27") (pin "8") (pinfunction "DP_8") (pintype "passive"))
      (node (ref "JP12") (pin "1") (pinfunction "1_1") (pintype "passive"))
      (node (ref "JP9") (pin "1") (pinfunction "1_1") (pintype "passive"))
      (node (ref "LED1") (pin "5") (pinfunction "DP_5") (pintype "passive"))
      (node (ref "LED10") (pin "5") (pinfunction "DP_5") (pintype "passive"))
      (node (ref "LED11") (pin "5") (pinfunction "DP_5") (pintype "passive"))
      (node (ref "LED12") (pin "5") (pinfunction "DP_5") (pintype "passive"))
      (node (ref "LED13") (pin "5") (pinfunction "DP_5") (pintype "passive"))
      (node (ref "LED14") (pin "5") (pinfunction "DP_5") (pintype "passive"))
      (node (ref "LED15") (pin "5") (pinfunction "DP_5") (pintype "passive"))
      (node (ref "LED2") (pin "5") (pinfunction "DP_5") (pintype "passive"))
      (node (ref "LED3") (pin "5") (pinfunction "DP_5") (pintype "passive"))
      (node (ref "LED4") (pin "5") (pinfunction "DP_5") (pintype "passive"))
      (node (ref "LED5") (pin "5") (pinfunction "DP_5") (pintype "passive"))
      (node (ref "LED6") (pin "5") (pinfunction "DP_5") (pintype "passive"))
      (node (ref "LED7") (pin "5") (pinfunction "DP_5") (pintype "passive"))
      (node (ref "LED8") (pin "5") (pinfunction "DP_5") (pintype "passive"))
      (node (ref "LED9") (pin "5") (pinfunction "DP_5") (pintype "passive"))
    )
    (net (code "49") (name "SEG_DP_SOURCE") (class "Default")
      (node (ref "JP7") (pin "1") (pinfunction "1_1") (pintype "passive"))
      (node (ref "M11") (pin "3") (pinfunction "D_3") (pintype "passive"))
    )
    (net (code "50") (name "SEG_E") (class "Default")
      (node (ref "D14") (pin "4") (pinfunction "E_4") (pintype "passive"))
      (node (ref "D15") (pin "4") (pinfunction "E_4") (pintype "passive"))
      (node (ref "D16") (pin "4") (pinfunction "E_4") (pintype "passive"))
      (node (ref "D17") (pin "4") (pinfunction "E_4") (pintype "passive"))
      (node (ref "D18") (pin "4") (pinfunction "E_4") (pintype "passive"))
      (node (ref "D19") (pin "4") (pinfunction "E_4") (pintype "passive"))
      (node (ref "D2") (pin "4") (pinfunction "E_4") (pintype "passive"))
      (node (ref "D20") (pin "4") (pinfunction "E_4") (pintype "passive"))
      (node (ref "D21") (pin "4") (pinfunction "E_4") (pintype "passive"))
      (node (ref "D22") (pin "4") (pinfunction "E_4") (pintype "passive"))
      (node (ref "D23") (pin "4") (pinfunction "E_4") (pintype "passive"))
      (node (ref "D24") (pin "4") (pinfunction "E_4") (pintype "passive"))
      (node (ref "D25") (pin "4") (pinfunction "E_4") (pintype "passive"))
      (node (ref "D26") (pin "4") (pinfunction "E_4") (pintype "passive"))
      (node (ref "D27") (pin "4") (pinfunction "E_4") (pintype "passive"))
      (node (ref "LED1") (pin "1") (pinfunction "E_1") (pintype "passive"))
      (node (ref "LED10") (pin "1") (pinfunction "E_1") (pintype "passive"))
      (node (ref "LED11") (pin "1") (pinfunction "E_1") (pintype "passive"))
      (node (ref "LED12") (pin "1") (pinfunction "E_1") (pintype "passive"))
      (node (ref "LED13") (pin "1") (pinfunction "E_1") (pintype "passive"))
      (node (ref "LED14") (pin "1") (pinfunction "E_1") (pintype "passive"))
      (node (ref "LED15") (pin "1") (pinfunction "E_1") (pintype "passive"))
      (node (ref "LED2") (pin "1") (pinfunction "E_1") (pintype "passive"))
      (node (ref "LED3") (pin "1") (pinfunction "E_1") (pintype "passive"))
      (node (ref "LED4") (pin "1") (pinfunction "E_1") (pintype "passive"))
      (node (ref "LED5") (pin "1") (pinfunction "E_1") (pintype "passive"))
      (node (ref "LED6") (pin "1") (pinfunction "E_1") (pintype "passive"))
      (node (ref "LED7") (pin "1") (pinfunction "E_1") (pintype "passive"))
      (node (ref "LED8") (pin "1") (pinfunction "E_1") (pintype "passive"))
      (node (ref "LED9") (pin "1") (pinfunction "E_1") (pintype "passive"))
      (node (ref "M8") (pin "3") (pinfunction "D_3") (pintype "passive"))
    )
    (net (code "51") (name "SEG_F") (class "Default")
      (node (ref "D14") (pin "2") (pinfunction "F_2") (pintype "passive"))
      (node (ref "D15") (pin "2") (pinfunction "F_2") (pintype "passive"))
      (node (ref "D16") (pin "2") (pinfunction "F_2") (pintype "passive"))
      (node (ref "D17") (pin "2") (pinfunction "F_2") (pintype "passive"))
      (node (ref "D18") (pin "2") (pinfunction "F_2") (pintype "passive"))
      (node (ref "D19") (pin "2") (pinfunction "F_2") (pintype "passive"))
      (node (ref "D2") (pin "2") (pinfunction "F_2") (pintype "passive"))
      (node (ref "D20") (pin "2") (pinfunction "F_2") (pintype "passive"))
      (node (ref "D21") (pin "2") (pinfunction "F_2") (pintype "passive"))
      (node (ref "D22") (pin "2") (pinfunction "F_2") (pintype "passive"))
      (node (ref "D23") (pin "2") (pinfunction "F_2") (pintype "passive"))
      (node (ref "D24") (pin "2") (pinfunction "F_2") (pintype "passive"))
      (node (ref "D25") (pin "2") (pinfunction "F_2") (pintype "passive"))
      (node (ref "D26") (pin "2") (pinfunction "F_2") (pintype "passive"))
      (node (ref "D27") (pin "2") (pinfunction "F_2") (pintype "passive"))
      (node (ref "LED1") (pin "9") (pinfunction "F_9") (pintype "passive"))
      (node (ref "LED10") (pin "9") (pinfunction "F_9") (pintype "passive"))
      (node (ref "LED11") (pin "9") (pinfunction "F_9") (pintype "passive"))
      (node (ref "LED12") (pin "9") (pinfunction "F_9") (pintype "passive"))
      (node (ref "LED13") (pin "9") (pinfunction "F_9") (pintype "passive"))
      (node (ref "LED14") (pin "9") (pinfunction "F_9") (pintype "passive"))
      (node (ref "LED15") (pin "9") (pinfunction "F_9") (pintype "passive"))
      (node (ref "LED2") (pin "9") (pinfunction "F_9") (pintype "passive"))
      (node (ref "LED3") (pin "9") (pinfunction "F_9") (pintype "passive"))
      (node (ref "LED4") (pin "9") (pinfunction "F_9") (pintype "passive"))
      (node (ref "LED5") (pin "9") (pinfunction "F_9") (pintype "passive"))
      (node (ref "LED6") (pin "9") (pinfunction "F_9") (pintype "passive"))
      (node (ref "LED7") (pin "9") (pinfunction "F_9") (pintype "passive"))
      (node (ref "LED8") (pin "9") (pinfunction "F_9") (pintype "passive"))
      (node (ref "LED9") (pin "9") (pinfunction "F_9") (pintype "passive"))
      (node (ref "M9") (pin "3") (pinfunction "D_3") (pintype "passive"))
    )
    (net (code "52") (name "SEG_G") (class "Default")
      (node (ref "D14") (pin "1") (pinfunction "G1_1") (pintype "passive"))
      (node (ref "D14") (pin "3") (pinfunction "G_3") (pintype "passive"))
      (node (ref "D15") (pin "1") (pinfunction "G1_1") (pintype "passive"))
      (node (ref "D15") (pin "3") (pinfunction "G_3") (pintype "passive"))
      (node (ref "D16") (pin "1") (pinfunction "G1_1") (pintype "passive"))
      (node (ref "D16") (pin "3") (pinfunction "G_3") (pintype "passive"))
      (node (ref "D17") (pin "1") (pinfunction "G1_1") (pintype "passive"))
      (node (ref "D17") (pin "3") (pinfunction "G_3") (pintype "passive"))
      (node (ref "D18") (pin "1") (pinfunction "G1_1") (pintype "passive"))
      (node (ref "D18") (pin "3") (pinfunction "G_3") (pintype "passive"))
      (node (ref "D19") (pin "1") (pinfunction "G1_1") (pintype "passive"))
      (node (ref "D19") (pin "3") (pinfunction "G_3") (pintype "passive"))
      (node (ref "D2") (pin "1") (pinfunction "G1_1") (pintype "passive"))
      (node (ref "D2") (pin "3") (pinfunction "G_3") (pintype "passive"))
      (node (ref "D20") (pin "1") (pinfunction "G1_1") (pintype "passive"))
      (node (ref "D20") (pin "3") (pinfunction "G_3") (pintype "passive"))
      (node (ref "D21") (pin "1") (pinfunction "G1_1") (pintype "passive"))
      (node (ref "D21") (pin "3") (pinfunction "G_3") (pintype "passive"))
      (node (ref "D22") (pin "1") (pinfunction "G1_1") (pintype "passive"))
      (node (ref "D22") (pin "3") (pinfunction "G_3") (pintype "passive"))
      (node (ref "D23") (pin "1") (pinfunction "G1_1") (pintype "passive"))
      (node (ref "D23") (pin "3") (pinfunction "G_3") (pintype "passive"))
      (node (ref "D24") (pin "1") (pinfunction "G1_1") (pintype "passive"))
      (node (ref "D24") (pin "3") (pinfunction "G_3") (pintype "passive"))
      (node (ref "D25") (pin "1") (pinfunction "G1_1") (pintype "passive"))
      (node (ref "D25") (pin "3") (pinfunction "G_3") (pintype "passive"))
      (node (ref "D26") (pin "1") (pinfunction "G1_1") (pintype "passive"))
      (node (ref "D26") (pin "3") (pinfunction "G_3") (pintype "passive"))
      (node (ref "D27") (pin "1") (pinfunction "G1_1") (pintype "passive"))
      (node (ref "D27") (pin "3") (pinfunction "G_3") (pintype "passive"))
      (node (ref "LED1") (pin "10") (pinfunction "G_10") (pintype "passive"))
      (node (ref "LED10") (pin "10") (pinfunction "G_10") (pintype "passive"))
      (node (ref "LED11") (pin "10") (pinfunction "G_10") (pintype "passive"))
      (node (ref "LED12") (pin "10") (pinfunction "G_10") (pintype "passive"))
      (node (ref "LED13") (pin "10") (pinfunction "G_10") (pintype "passive"))
      (node (ref "LED14") (pin "10") (pinfunction "G_10") (pintype "passive"))
      (node (ref "LED15") (pin "10") (pinfunction "G_10") (pintype "passive"))
      (node (ref "LED2") (pin "10") (pinfunction "G_10") (pintype "passive"))
      (node (ref "LED3") (pin "10") (pinfunction "G_10") (pintype "passive"))
      (node (ref "LED4") (pin "10") (pinfunction "G_10") (pintype "passive"))
      (node (ref "LED5") (pin "10") (pinfunction "G_10") (pintype "passive"))
      (node (ref "LED6") (pin "10") (pinfunction "G_10") (pintype "passive"))
      (node (ref "LED7") (pin "10") (pinfunction "G_10") (pintype "passive"))
      (node (ref "LED8") (pin "10") (pinfunction "G_10") (pintype "passive"))
      (node (ref "LED9") (pin "10") (pinfunction "G_10") (pintype "passive"))
      (node (ref "M10") (pin "3") (pinfunction "D_3") (pintype "passive"))
    )
  )
)
